# TinkerAccess_RGB_LED_Driver.net
KiCad netlist of a schematic drawn in EAGLE
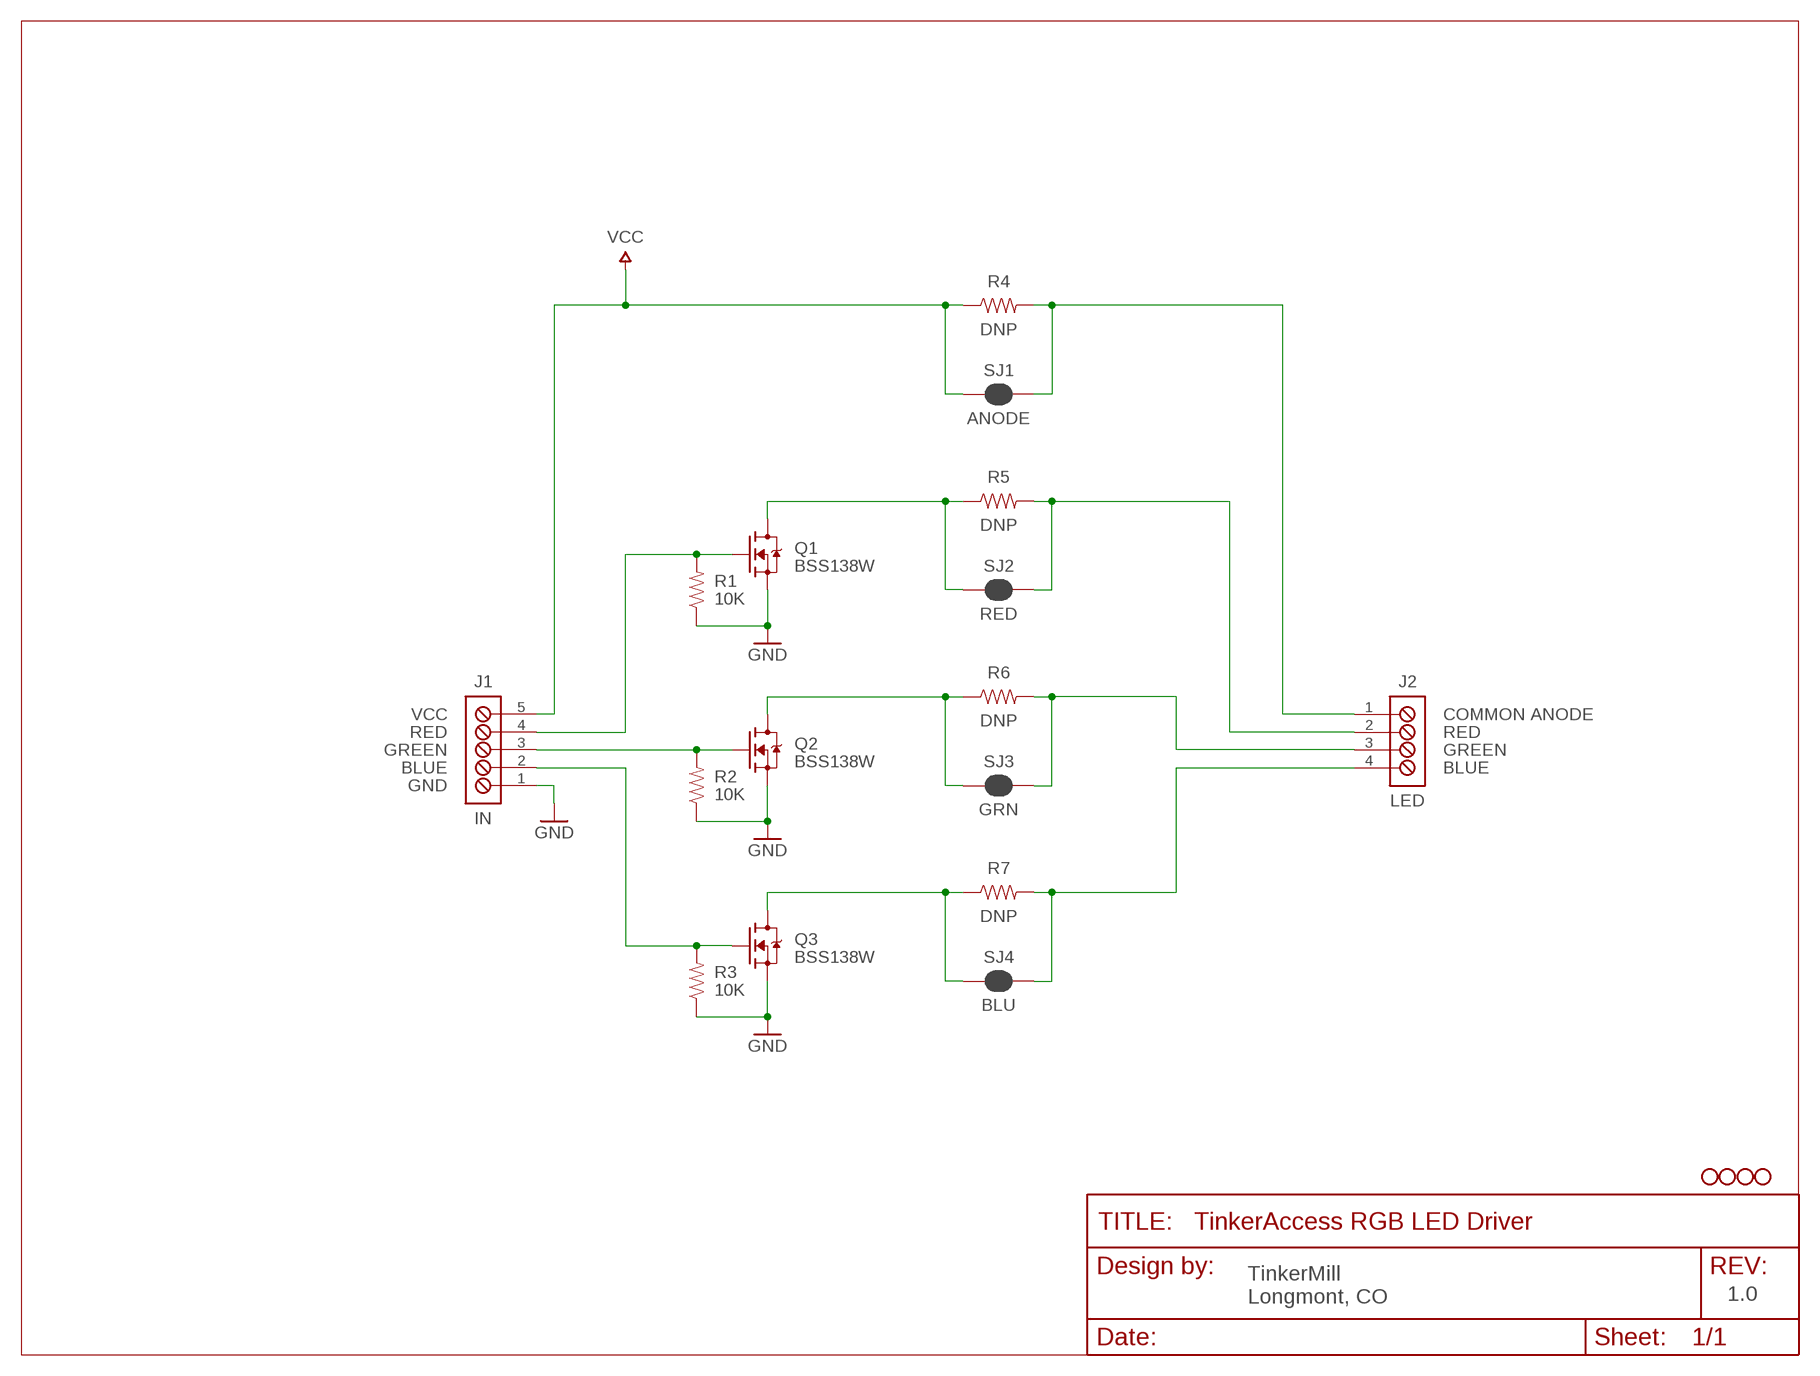
[diagram p0: schematic, sheet 1]

(export (version "E")
  (design (tool "Eeschema 10.0.6"))
  (components
    (comp (ref "J1")
      (value "IN")
      (footprint "eagle-import:ON_SHORE_OSTVN05A150")
      (libsource (lib "eagle-import") (part "TB_5X1_ON_SHORE_OSTVN05A150"))
    )
    (comp (ref "J2")
      (value "LED")
      (footprint "eagle-import:ON_SHORE_OSTVN04A150")
      (libsource (lib "eagle-import") (part "TB_4X1_ON_SHORE_OSTVN04A150"))
    )
    (comp (ref "Q1")
      (value "BSS138W")
      (footprint "eagle-import:SOT323")
      (libsource (lib "eagle-import") (part "N_MOSFET_BSS138W"))
    )
    (comp (ref "Q2")
      (value "BSS138W")
      (footprint "eagle-import:SOT323")
      (libsource (lib "eagle-import") (part "N_MOSFET_BSS138W"))
    )
    (comp (ref "Q3")
      (value "BSS138W")
      (footprint "eagle-import:SOT323")
      (libsource (lib "eagle-import") (part "N_MOSFET_BSS138W"))
    )
    (comp (ref "R1")
      (value "10K")
      (footprint "eagle-import:0603")
      (libsource (lib "eagle-import") (part "RESISTOR_0603"))
    )
    (comp (ref "R2")
      (value "10K")
      (footprint "eagle-import:0603")
      (libsource (lib "eagle-import") (part "RESISTOR_0603"))
    )
    (comp (ref "R3")
      (value "10K")
      (footprint "eagle-import:0603")
      (libsource (lib "eagle-import") (part "RESISTOR_0603"))
    )
    (comp (ref "R4")
      (value "DNP")
      (footprint "eagle-import:0603")
      (libsource (lib "eagle-import") (part "RESISTOR_0603"))
    )
    (comp (ref "R5")
      (value "DNP")
      (footprint "eagle-import:0603")
      (libsource (lib "eagle-import") (part "RESISTOR_0603"))
    )
    (comp (ref "R6")
      (value "DNP")
      (footprint "eagle-import:0603")
      (libsource (lib "eagle-import") (part "RESISTOR_0603"))
    )
    (comp (ref "R7")
      (value "DNP")
      (footprint "eagle-import:0603")
      (libsource (lib "eagle-import") (part "RESISTOR_0603"))
    )
    (comp (ref "SJ1")
      (value "ANODE")
      (footprint "eagle-import:JMP_PAD_2X1_CLOSED_BY_PASTE")
      (libsource (lib "eagle-import") (part "JMP_PAD_2X1_CLOSED_BY_PASTE_NORMAL"))
    )
    (comp (ref "SJ2")
      (value "RED")
      (footprint "eagle-import:JMP_PAD_2X1_CLOSED_BY_PASTE")
      (libsource (lib "eagle-import") (part "JMP_PAD_2X1_CLOSED_BY_PASTE_NORMAL"))
    )
    (comp (ref "SJ3")
      (value "GRN")
      (footprint "eagle-import:JMP_PAD_2X1_CLOSED_BY_PASTE")
      (libsource (lib "eagle-import") (part "JMP_PAD_2X1_CLOSED_BY_PASTE_NORMAL"))
    )
    (comp (ref "SJ4")
      (value "BLU")
      (footprint "eagle-import:JMP_PAD_2X1_CLOSED_BY_PASTE")
      (libsource (lib "eagle-import") (part "JMP_PAD_2X1_CLOSED_BY_PASTE_NORMAL"))
    )
    (comp (ref "STANDOFF1")
      (value "STANDOFF_2.3MM_NO_CU")
      (footprint "eagle-import:STANDOFF_2.3MM_NO_CU")
      (libsource (lib "eagle-import") (part "STANDOFF_2.3MM_NO_CU"))
    )
    (comp (ref "STANDOFF2")
      (value "STANDOFF_2.3MM_NO_CU")
      (footprint "eagle-import:STANDOFF_2.3MM_NO_CU")
      (libsource (lib "eagle-import") (part "STANDOFF_2.3MM_NO_CU"))
    )
    (comp (ref "STANDOFF3")
      (value "STANDOFF_2.3MM_NO_CU")
      (footprint "eagle-import:STANDOFF_2.3MM_NO_CU")
      (libsource (lib "eagle-import") (part "STANDOFF_2.3MM_NO_CU"))
    )
    (comp (ref "STANDOFF4")
      (value "STANDOFF_2.3MM_NO_CU")
      (footprint "eagle-import:STANDOFF_2.3MM_NO_CU")
      (libsource (lib "eagle-import") (part "STANDOFF_2.3MM_NO_CU"))
    )
  )
  (nets
    (net (code "1") (name "GND") (class "Default")
      (node (ref "J1") (pin "1") (pinfunction "1_1") (pintype "passive"))
      (node (ref "Q1") (pin "2") (pinfunction "S_2") (pintype "passive"))
      (node (ref "Q2") (pin "2") (pinfunction "S_2") (pintype "passive"))
      (node (ref "Q3") (pin "2") (pinfunction "S_2") (pintype "passive"))
      (node (ref "R1") (pin "1") (pinfunction "1_1") (pintype "passive"))
      (node (ref "R2") (pin "1") (pinfunction "1_1") (pintype "passive"))
      (node (ref "R3") (pin "1") (pinfunction "1_1") (pintype "passive"))
    )
    (net (code "2") (name "Net-(J2-Pad1)") (class "Default")
      (node (ref "J2") (pin "1") (pinfunction "1_1") (pintype "passive"))
      (node (ref "R4") (pin "2") (pinfunction "2_2") (pintype "passive"))
      (node (ref "SJ1") (pin "2") (pinfunction "2_2") (pintype "passive"))
    )
    (net (code "3") (name "Net-(J2-Pad2)") (class "Default")
      (node (ref "J2") (pin "2") (pinfunction "2_2") (pintype "passive"))
      (node (ref "R5") (pin "2") (pinfunction "2_2") (pintype "passive"))
      (node (ref "SJ2") (pin "2") (pinfunction "2_2") (pintype "passive"))
    )
    (net (code "4") (name "Net-(J2-Pad3)") (class "Default")
      (node (ref "J2") (pin "3") (pinfunction "3_3") (pintype "passive"))
      (node (ref "R6") (pin "2") (pinfunction "2_2") (pintype "passive"))
      (node (ref "SJ3") (pin "2") (pinfunction "2_2") (pintype "passive"))
    )
    (net (code "5") (name "Net-(J2-Pad4)") (class "Default")
      (node (ref "J2") (pin "4") (pinfunction "4_4") (pintype "passive"))
      (node (ref "R7") (pin "2") (pinfunction "2_2") (pintype "passive"))
      (node (ref "SJ4") (pin "2") (pinfunction "2_2") (pintype "passive"))
    )
    (net (code "6") (name "Net-(Q1-D)") (class "Default")
      (node (ref "Q1") (pin "3") (pinfunction "D_3") (pintype "passive"))
      (node (ref "R5") (pin "1") (pinfunction "1_1") (pintype "passive"))
      (node (ref "SJ2") (pin "1") (pinfunction "1_1") (pintype "passive"))
    )
    (net (code "7") (name "Net-(Q1-G)") (class "Default")
      (node (ref "J1") (pin "4") (pinfunction "4_4") (pintype "passive"))
      (node (ref "Q1") (pin "1") (pinfunction "G_1") (pintype "passive"))
      (node (ref "R1") (pin "2") (pinfunction "2_2") (pintype "passive"))
    )
    (net (code "8") (name "Net-(Q2-D)") (class "Default")
      (node (ref "Q2") (pin "3") (pinfunction "D_3") (pintype "passive"))
      (node (ref "R6") (pin "1") (pinfunction "1_1") (pintype "passive"))
      (node (ref "SJ3") (pin "1") (pinfunction "1_1") (pintype "passive"))
    )
    (net (code "9") (name "Net-(Q2-G)") (class "Default")
      (node (ref "J1") (pin "3") (pinfunction "3_3") (pintype "passive"))
      (node (ref "Q2") (pin "1") (pinfunction "G_1") (pintype "passive"))
      (node (ref "R2") (pin "2") (pinfunction "2_2") (pintype "passive"))
    )
    (net (code "10") (name "Net-(Q3-D)") (class "Default")
      (node (ref "Q3") (pin "3") (pinfunction "D_3") (pintype "passive"))
      (node (ref "R7") (pin "1") (pinfunction "1_1") (pintype "passive"))
      (node (ref "SJ4") (pin "1") (pinfunction "1_1") (pintype "passive"))
    )
    (net (code "11") (name "Net-(Q3-G)") (class "Default")
      (node (ref "J1") (pin "2") (pinfunction "2_2") (pintype "passive"))
      (node (ref "Q3") (pin "1") (pinfunction "G_1") (pintype "passive"))
      (node (ref "R3") (pin "2") (pinfunction "2_2") (pintype "passive"))
    )
    (net (code "12") (name "VCC") (class "Default")
      (node (ref "J1") (pin "5") (pinfunction "5_5") (pintype "passive"))
      (node (ref "R4") (pin "1") (pinfunction "1_1") (pintype "passive"))
      (node (ref "SJ1") (pin "1") (pinfunction "1_1") (pintype "passive"))
    )
  )
)
